# SCB_PLLs.net
KiCad netlist of a schematic drawn in Altium Designer
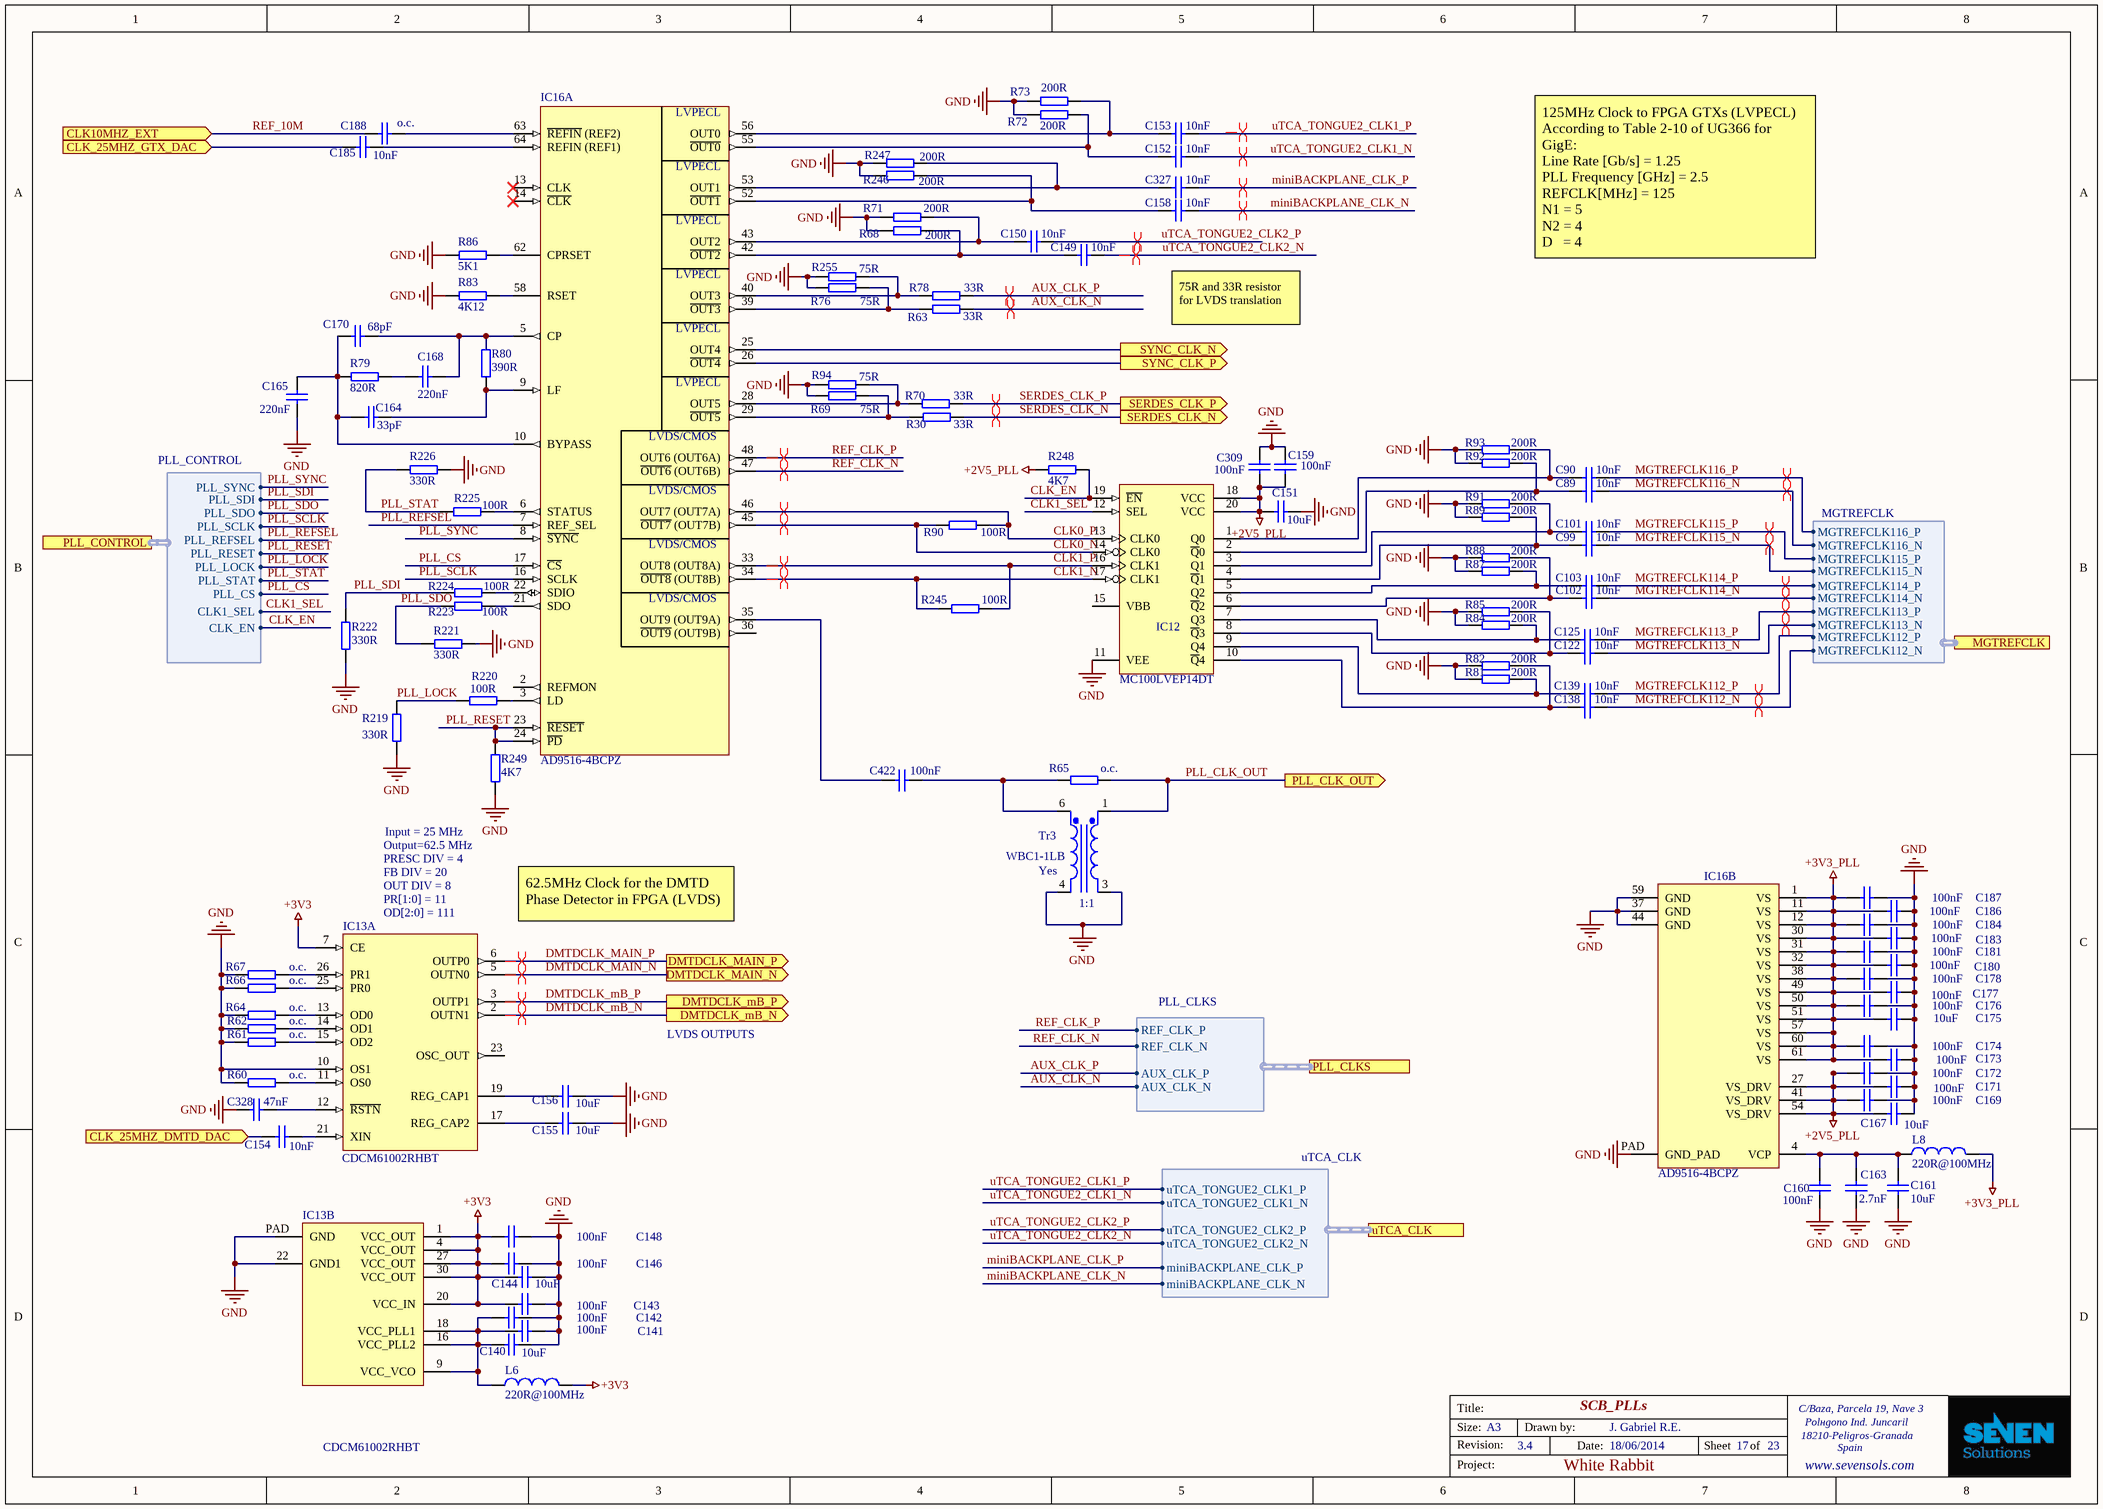
[diagram p0: SCB_PLLs.SchDoc]

(export (version "E")
  (design (tool "Eeschema 10.0.6"))
  (components
    (comp (ref "C89")
      (value "10nF")
      (footprint "CC1005-0402")
      (description "Capacitor")
      (fields (field (name "TOLERANCE") "±10%") (field (name "VOLTAGE") "25V"))
      (libsource (lib "wr_switch") (part "Cap"))
    )
    (comp (ref "C90")
      (value "10nF")
      (footprint "CC1005-0402")
      (description "Capacitor")
      (fields (field (name "TOLERANCE") "±10%") (field (name "VOLTAGE") "25V"))
      (libsource (lib "wr_switch") (part "Cap"))
    )
    (comp (ref "C99")
      (value "10nF")
      (footprint "CC1005-0402")
      (description "Capacitor")
      (fields (field (name "TOLERANCE") "±10%") (field (name "VOLTAGE") "25V"))
      (libsource (lib "wr_switch") (part "Cap"))
    )
    (comp (ref "C101")
      (value "10nF")
      (footprint "CC1005-0402")
      (description "Capacitor")
      (fields (field (name "TOLERANCE") "±10%") (field (name "VOLTAGE") "25V"))
      (libsource (lib "wr_switch") (part "Cap"))
    )
    (comp (ref "C102")
      (value "10nF")
      (footprint "CC1005-0402")
      (description "Capacitor")
      (fields (field (name "TOLERANCE") "±10%") (field (name "VOLTAGE") "25V"))
      (libsource (lib "wr_switch") (part "Cap"))
    )
    (comp (ref "C103")
      (value "10nF")
      (footprint "CC1005-0402")
      (description "Capacitor")
      (fields (field (name "TOLERANCE") "±10%") (field (name "VOLTAGE") "25V"))
      (libsource (lib "wr_switch") (part "Cap"))
    )
    (comp (ref "C122")
      (value "10nF")
      (footprint "CC1005-0402")
      (description "Capacitor")
      (fields (field (name "TOLERANCE") "±10%") (field (name "VOLTAGE") "25V"))
      (libsource (lib "wr_switch") (part "Cap"))
    )
    (comp (ref "C125")
      (value "10nF")
      (footprint "CC1005-0402")
      (description "Capacitor")
      (fields (field (name "TOLERANCE") "±10%") (field (name "VOLTAGE") "25V"))
      (libsource (lib "wr_switch") (part "Cap"))
    )
    (comp (ref "C138")
      (value "10nF")
      (footprint "CC1005-0402")
      (description "Capacitor")
      (fields (field (name "TOLERANCE") "±10%") (field (name "VOLTAGE") "25V"))
      (libsource (lib "wr_switch") (part "Cap"))
    )
    (comp (ref "C139")
      (value "10nF")
      (footprint "CC1005-0402")
      (description "Capacitor")
      (fields (field (name "TOLERANCE") "±10%") (field (name "VOLTAGE") "25V"))
      (libsource (lib "wr_switch") (part "Cap"))
    )
    (comp (ref "C140")
      (value "10uF")
      (footprint "CC1608-0603")
      (description "Capacitor")
      (fields (field (name "TOLERANCE") "±20%") (field (name "VOLTAGE") "6.3V"))
      (libsource (lib "wr_switch") (part "Cap"))
    )
    (comp (ref "C141")
      (value "100nF")
      (footprint "CC1005-0402")
      (description "Capacitor")
      (fields (field (name "TOLERANCE") "±10%") (field (name "VOLTAGE") "16V"))
      (libsource (lib "wr_switch") (part "Cap"))
    )
    (comp (ref "C142")
      (value "100nF")
      (footprint "CC1005-0402")
      (description "Capacitor")
      (fields (field (name "TOLERANCE") "±10%") (field (name "VOLTAGE") "16V"))
      (libsource (lib "wr_switch") (part "Cap"))
    )
    (comp (ref "C143")
      (value "100nF")
      (footprint "CC1005-0402")
      (description "Capacitor")
      (fields (field (name "TOLERANCE") "±10%") (field (name "VOLTAGE") "16V"))
      (libsource (lib "wr_switch") (part "Cap"))
    )
    (comp (ref "C144")
      (value "10uF")
      (footprint "CC1608-0603")
      (description "Capacitor")
      (fields (field (name "TOLERANCE") "±20%") (field (name "VOLTAGE") "6.3V"))
      (libsource (lib "wr_switch") (part "Cap"))
    )
    (comp (ref "C146")
      (value "100nF")
      (footprint "CC1005-0402")
      (description "Capacitor")
      (fields (field (name "TOLERANCE") "±10%") (field (name "VOLTAGE") "16V"))
      (libsource (lib "wr_switch") (part "Cap"))
    )
    (comp (ref "C148")
      (value "100nF")
      (footprint "CC1005-0402")
      (description "Capacitor")
      (fields (field (name "TOLERANCE") "±10%") (field (name "VOLTAGE") "16V"))
      (libsource (lib "wr_switch") (part "Cap"))
    )
    (comp (ref "C149")
      (value "10nF")
      (footprint "CC1005-0402")
      (description "Capacitor")
      (fields (field (name "TOLERANCE") "±10%") (field (name "VOLTAGE") "25V"))
      (libsource (lib "wr_switch") (part "Cap"))
    )
    (comp (ref "C150")
      (value "10nF")
      (footprint "CC1005-0402")
      (description "Capacitor")
      (fields (field (name "TOLERANCE") "±10%") (field (name "VOLTAGE") "25V"))
      (libsource (lib "wr_switch") (part "Cap"))
    )
    (comp (ref "C151")
      (value "10uF")
      (footprint "CC1608-0603")
      (description "Capacitor")
      (fields (field (name "TOLERANCE") "±20%") (field (name "VOLTAGE") "6.3V"))
      (libsource (lib "wr_switch") (part "Cap"))
    )
    (comp (ref "C152")
      (value "10nF")
      (footprint "CC1005-0402")
      (description "Capacitor")
      (fields (field (name "TOLERANCE") "±10%") (field (name "VOLTAGE") "25V"))
      (libsource (lib "wr_switch") (part "Cap"))
    )
    (comp (ref "C153")
      (value "10nF")
      (footprint "CC1005-0402")
      (description "Capacitor")
      (fields (field (name "TOLERANCE") "±10%") (field (name "VOLTAGE") "25V"))
      (libsource (lib "wr_switch") (part "Cap"))
    )
    (comp (ref "C154")
      (value "10nF")
      (footprint "CC1005-0402")
      (description "Capacitor")
      (fields (field (name "TOLERANCE") "±10%") (field (name "VOLTAGE") "25V"))
      (libsource (lib "wr_switch") (part "Cap"))
    )
    (comp (ref "C155")
      (value "10uF")
      (footprint "CC1608-0603")
      (description "Capacitor")
      (fields (field (name "TOLERANCE") "±20%") (field (name "VOLTAGE") "6.3V"))
      (libsource (lib "wr_switch") (part "Cap"))
    )
    (comp (ref "C156")
      (value "10uF")
      (footprint "CC1608-0603")
      (description "Capacitor")
      (fields (field (name "TOLERANCE") "±20%") (field (name "VOLTAGE") "6.3V"))
      (libsource (lib "wr_switch") (part "Cap"))
    )
    (comp (ref "C158")
      (value "10nF")
      (footprint "CC1005-0402")
      (description "Capacitor")
      (fields (field (name "TOLERANCE") "±10%") (field (name "VOLTAGE") "25V"))
      (libsource (lib "wr_switch") (part "Cap"))
    )
    (comp (ref "C159")
      (value "100nF")
      (footprint "CC1005-0402")
      (description "Capacitor")
      (fields (field (name "TOLERANCE") "±10%") (field (name "VOLTAGE") "16V"))
      (libsource (lib "wr_switch") (part "Cap"))
    )
    (comp (ref "C160")
      (value "100nF")
      (footprint "CC1005-0402")
      (description "Capacitor")
      (fields (field (name "TOLERANCE") "±10%") (field (name "VOLTAGE") "16V"))
      (libsource (lib "wr_switch") (part "Cap"))
    )
    (comp (ref "C161")
      (value "10uF")
      (footprint "CC1608-0603")
      (description "Capacitor")
      (fields (field (name "TOLERANCE") "±20%") (field (name "VOLTAGE") "6.3V"))
      (libsource (lib "wr_switch") (part "Cap"))
    )
    (comp (ref "C163")
      (value "2.7nF")
      (footprint "CC1005-0402")
      (description "Capacitor")
      (fields (field (name "TOLERANCE") "±10%") (field (name "VOLTAGE") "50V"))
      (libsource (lib "wr_switch") (part "Cap"))
    )
    (comp (ref "C164")
      (value "33pF")
      (footprint "CC1608-0603")
      (description "Capacitor")
      (fields (field (name "TOLERANCE") "±5%") (field (name "VOLTAGE") "50V"))
      (libsource (lib "wr_switch") (part "Cap"))
    )
    (comp (ref "C165")
      (value "220nF")
      (footprint "CC1608-0603")
      (description "Capacitor")
      (fields (field (name "TOLERANCE") "±10%") (field (name "VOLTAGE") "10V"))
      (libsource (lib "wr_switch") (part "Cap"))
    )
    (comp (ref "C167")
      (value "10uF")
      (footprint "CC1608-0603")
      (description "Capacitor")
      (fields (field (name "TOLERANCE") "±20%") (field (name "VOLTAGE") "6.3V"))
      (libsource (lib "wr_switch") (part "Cap"))
    )
    (comp (ref "C168")
      (value "220nF")
      (footprint "CC1608-0603")
      (description "Capacitor")
      (fields (field (name "TOLERANCE") "±10%") (field (name "VOLTAGE") "10V"))
      (libsource (lib "wr_switch") (part "Cap"))
    )
    (comp (ref "C169")
      (value "100nF")
      (footprint "CC1005-0402")
      (description "Capacitor")
      (fields (field (name "TOLERANCE") "±10%") (field (name "VOLTAGE") "16V"))
      (libsource (lib "wr_switch") (part "Cap"))
    )
    (comp (ref "C170")
      (value "68pF")
      (footprint "CC1608-0603")
      (description "Capacitor")
      (fields (field (name "TOLERANCE") "±5%") (field (name "VOLTAGE") "50V"))
      (libsource (lib "wr_switch") (part "Cap"))
    )
    (comp (ref "C171")
      (value "100nF")
      (footprint "CC1005-0402")
      (description "Capacitor")
      (fields (field (name "TOLERANCE") "±10%") (field (name "VOLTAGE") "16V"))
      (libsource (lib "wr_switch") (part "Cap"))
    )
    (comp (ref "C172")
      (value "100nF")
      (footprint "CC1005-0402")
      (description "Capacitor")
      (fields (field (name "TOLERANCE") "±10%") (field (name "VOLTAGE") "16V"))
      (libsource (lib "wr_switch") (part "Cap"))
    )
    (comp (ref "C173")
      (value "100nF")
      (footprint "CC1005-0402")
      (description "Capacitor")
      (fields (field (name "TOLERANCE") "±10%") (field (name "VOLTAGE") "16V"))
      (libsource (lib "wr_switch") (part "Cap"))
    )
    (comp (ref "C174")
      (value "100nF")
      (footprint "CC1005-0402")
      (description "Capacitor")
      (fields (field (name "TOLERANCE") "±10%") (field (name "VOLTAGE") "16V"))
      (libsource (lib "wr_switch") (part "Cap"))
    )
    (comp (ref "C175")
      (value "10uF")
      (footprint "CC1608-0603")
      (description "Capacitor")
      (fields (field (name "TOLERANCE") "±20%") (field (name "VOLTAGE") "6.3V"))
      (libsource (lib "wr_switch") (part "Cap"))
    )
    (comp (ref "C176")
      (value "100nF")
      (footprint "CC1005-0402")
      (description "Capacitor")
      (fields (field (name "TOLERANCE") "±10%") (field (name "VOLTAGE") "16V"))
      (libsource (lib "wr_switch") (part "Cap"))
    )
    (comp (ref "C177")
      (value "100nF")
      (footprint "CC1005-0402")
      (description "Capacitor")
      (fields (field (name "TOLERANCE") "±10%") (field (name "VOLTAGE") "16V"))
      (libsource (lib "wr_switch") (part "Cap"))
    )
    (comp (ref "C178")
      (value "100nF")
      (footprint "CC1005-0402")
      (description "Capacitor")
      (fields (field (name "TOLERANCE") "±10%") (field (name "VOLTAGE") "16V"))
      (libsource (lib "wr_switch") (part "Cap"))
    )
    (comp (ref "C180")
      (value "100nF")
      (footprint "CC1005-0402")
      (description "Capacitor")
      (fields (field (name "TOLERANCE") "±10%") (field (name "VOLTAGE") "16V"))
      (libsource (lib "wr_switch") (part "Cap"))
    )
    (comp (ref "C181")
      (value "100nF")
      (footprint "CC1005-0402")
      (description "Capacitor")
      (fields (field (name "TOLERANCE") "±10%") (field (name "VOLTAGE") "16V"))
      (libsource (lib "wr_switch") (part "Cap"))
    )
    (comp (ref "C183")
      (value "100nF")
      (footprint "CC1005-0402")
      (description "Capacitor")
      (fields (field (name "TOLERANCE") "±10%") (field (name "VOLTAGE") "16V"))
      (libsource (lib "wr_switch") (part "Cap"))
    )
    (comp (ref "C184")
      (value "100nF")
      (footprint "CC1005-0402")
      (description "Capacitor")
      (fields (field (name "TOLERANCE") "±10%") (field (name "VOLTAGE") "16V"))
      (libsource (lib "wr_switch") (part "Cap"))
    )
    (comp (ref "C185")
      (value "10nF")
      (footprint "CC1005-0402")
      (description "Capacitor")
      (fields (field (name "TOLERANCE") "±10%") (field (name "VOLTAGE") "25V"))
      (libsource (lib "wr_switch") (part "Cap"))
    )
    (comp (ref "C186")
      (value "100nF")
      (footprint "CC1005-0402")
      (description "Capacitor")
      (fields (field (name "TOLERANCE") "±10%") (field (name "VOLTAGE") "16V"))
      (libsource (lib "wr_switch") (part "Cap"))
    )
    (comp (ref "C187")
      (value "100nF")
      (footprint "CC1005-0402")
      (description "Capacitor")
      (fields (field (name "TOLERANCE") "±10%") (field (name "VOLTAGE") "16V"))
      (libsource (lib "wr_switch") (part "Cap"))
    )
    (comp (ref "C188")
      (value "o.c.")
      (footprint "CC1005-0402")
      (description "Capacitor")
      (fields (field (name "TOLERANCE") "±10%") (field (name "VOLTAGE") "25V"))
      (libsource (lib "wr_switch") (part "Cap"))
    )
    (comp (ref "C309")
      (value "100nF")
      (footprint "CC1005-0402")
      (description "Capacitor")
      (fields (field (name "TOLERANCE") "±10%") (field (name "VOLTAGE") "16V"))
      (libsource (lib "wr_switch") (part "Cap"))
    )
    (comp (ref "C327")
      (value "10nF")
      (footprint "CC1005-0402")
      (description "Capacitor")
      (fields (field (name "TOLERANCE") "±10%") (field (name "VOLTAGE") "25V"))
      (libsource (lib "wr_switch") (part "Cap"))
    )
    (comp (ref "C328")
      (value "47nF")
      (footprint "CC1005-0402")
      (description "Capacitor")
      (fields (field (name "TOLERANCE") "±10%") (field (name "VOLTAGE") "25V"))
      (libsource (lib "wr_switch") (part "Cap"))
    )
    (comp (ref "C422")
      (value "100nF")
      (footprint "CC1005-0402")
      (description "Capacitor")
      (fields (field (name "TOLERANCE") "±10%") (field (name "VOLTAGE") "16V"))
      (libsource (lib "wr_switch") (part "Cap"))
    )
    (comp (ref "IC12")
      (value "MC100LVEP14DT")
      (footprint "948E-02_N")
      (description "Low-Voltage 1:5 Differential LVECL/LVPECL/LVEPECL/HSTL Clock Driver")
      (libsource (lib "ON Semi Peripheral Clock Generator") (part "MC100LVEP14DT"))
    )
    (comp (ref "IC13")
      (value "CDCM61002RHBT")
      (footprint "QFN32_POWERPAD")
      (description "Low Jitter Clock Generator, Two Outpust, Integrated VCO")
      (fields (field (name "MANUFACTURER") "Texas Instruments"))
      (libsource (lib "wr_switch") (part "CDCM61002"))
    )
    (comp (ref "IC16")
      (value "AD9516-4BCPZ")
      (footprint "QFN50P900X900X100-64M")
      (description "PLL with clock fanout")
      (libsource (lib "wr_switch") (part "AD9516"))
    )
    (comp (ref "L6")
      (value "220R@100MHz Ferrite Bead")
      (footprint "0603")
      (description "ferrite bead")
      (fields (field (name "IMPEDANCE") "220R@100MHz"))
      (libsource (lib "wr_switch") (part "L_FERRITE_BEAD"))
    )
    (comp (ref "L8")
      (value "220R@100MHz Ferrite Bead")
      (footprint "0603")
      (description "ferrite bead")
      (fields (field (name "IMPEDANCE") "220R@100MHz"))
      (libsource (lib "wr_switch") (part "L_FERRITE_BEAD"))
    )
    (comp (ref "R30")
      (value "33R")
      (footprint "0402")
      (description "SMD Resistor")
      (fields (field (name "TOLERANCE") "±1%"))
      (libsource (lib "wr_switch") (part "RES_SMD"))
    )
    (comp (ref "R60")
      (value "o.c.")
      (footprint "0402")
      (description "SMD Resistor")
      (libsource (lib "wr_switch") (part "RES_SMD"))
    )
    (comp (ref "R61")
      (value "o.c.")
      (footprint "0402")
      (description "SMD Resistor")
      (libsource (lib "wr_switch") (part "RES_SMD"))
    )
    (comp (ref "R62")
      (value "o.c.")
      (footprint "0402")
      (description "SMD Resistor")
      (libsource (lib "wr_switch") (part "RES_SMD"))
    )
    (comp (ref "R63")
      (value "33R")
      (footprint "0402")
      (description "SMD Resistor")
      (fields (field (name "TOLERANCE") "±1%"))
      (libsource (lib "wr_switch") (part "RES_SMD"))
    )
    (comp (ref "R64")
      (value "o.c.")
      (footprint "0402")
      (description "SMD Resistor")
      (libsource (lib "wr_switch") (part "RES_SMD"))
    )
    (comp (ref "R65")
      (value "o.c.")
      (footprint "0402")
      (description "SMD Resistor")
      (libsource (lib "wr_switch") (part "RES_SMD"))
    )
    (comp (ref "R66")
      (value "o.c.")
      (footprint "0402")
      (description "SMD Resistor")
      (libsource (lib "wr_switch") (part "RES_SMD"))
    )
    (comp (ref "R67")
      (value "o.c.")
      (footprint "0402")
      (description "SMD Resistor")
      (libsource (lib "wr_switch") (part "RES_SMD"))
    )
    (comp (ref "R68")
      (value "200R")
      (footprint "0402")
      (description "SMD Resistor")
      (fields (field (name "TOLERANCE") "±1%"))
      (libsource (lib "wr_switch") (part "RES_SMD"))
    )
    (comp (ref "R69")
      (value "75R")
      (footprint "0402")
      (description "SMD Resistor")
      (fields (field (name "TOLERANCE") "±1%"))
      (libsource (lib "wr_switch") (part "RES_SMD"))
    )
    (comp (ref "R70")
      (value "33R")
      (footprint "0402")
      (description "SMD Resistor")
      (fields (field (name "TOLERANCE") "±1%"))
      (libsource (lib "wr_switch") (part "RES_SMD"))
    )
    (comp (ref "R71")
      (value "200R")
      (footprint "0402")
      (description "SMD Resistor")
      (fields (field (name "TOLERANCE") "±1%"))
      (libsource (lib "wr_switch") (part "RES_SMD"))
    )
    (comp (ref "R72")
      (value "200R")
      (footprint "0402")
      (description "SMD Resistor")
      (fields (field (name "TOLERANCE") "±1%"))
      (libsource (lib "wr_switch") (part "RES_SMD"))
    )
    (comp (ref "R73")
      (value "200R")
      (footprint "0402")
      (description "SMD Resistor")
      (fields (field (name "TOLERANCE") "±1%"))
      (libsource (lib "wr_switch") (part "RES_SMD"))
    )
    (comp (ref "R76")
      (value "75R")
      (footprint "0402")
      (description "SMD Resistor")
      (fields (field (name "TOLERANCE") "±1%"))
      (libsource (lib "wr_switch") (part "RES_SMD"))
    )
    (comp (ref "R78")
      (value "33R")
      (footprint "0402")
      (description "SMD Resistor")
      (fields (field (name "TOLERANCE") "±1%"))
      (libsource (lib "wr_switch") (part "RES_SMD"))
    )
    (comp (ref "R79")
      (value "820R")
      (footprint "0603")
      (description "SMD Resistor")
      (fields (field (name "TOLERANCE") "±1%"))
      (libsource (lib "wr_switch") (part "RES_SMD"))
    )
    (comp (ref "R80")
      (value "390R")
      (footprint "0603")
      (description "SMD Resistor")
      (fields (field (name "TOLERANCE") "±1%"))
      (libsource (lib "wr_switch") (part "RES_SMD"))
    )
    (comp (ref "R81")
      (value "200R")
      (footprint "0402")
      (description "SMD Resistor")
      (fields (field (name "TOLERANCE") "±1%"))
      (libsource (lib "wr_switch") (part "RES_SMD"))
    )
    (comp (ref "R82")
      (value "200R")
      (footprint "0402")
      (description "SMD Resistor")
      (fields (field (name "TOLERANCE") "±1%"))
      (libsource (lib "wr_switch") (part "RES_SMD"))
    )
    (comp (ref "R83")
      (value "4K12")
      (footprint "0402")
      (description "SMD Resistor")
      (fields (field (name "TOLERANCE") "±1%"))
      (libsource (lib "wr_switch") (part "RES_SMD"))
    )
    (comp (ref "R84")
      (value "200R")
      (footprint "0402")
      (description "SMD Resistor")
      (fields (field (name "TOLERANCE") "±1%"))
      (libsource (lib "wr_switch") (part "RES_SMD"))
    )
    (comp (ref "R85")
      (value "200R")
      (footprint "0402")
      (description "SMD Resistor")
      (fields (field (name "TOLERANCE") "±1%"))
      (libsource (lib "wr_switch") (part "RES_SMD"))
    )
    (comp (ref "R86")
      (value "5K1")
      (footprint "0402")
      (description "SMD Resistor")
      (fields (field (name "TOLERANCE") "±1%"))
      (libsource (lib "wr_switch") (part "RES_SMD"))
    )
    (comp (ref "R87")
      (value "200R")
      (footprint "0402")
      (description "SMD Resistor")
      (fields (field (name "TOLERANCE") "±1%"))
      (libsource (lib "wr_switch") (part "RES_SMD"))
    )
    (comp (ref "R88")
      (value "200R")
      (footprint "0402")
      (description "SMD Resistor")
      (fields (field (name "TOLERANCE") "±1%"))
      (libsource (lib "wr_switch") (part "RES_SMD"))
    )
    (comp (ref "R89")
      (value "200R")
      (footprint "0402")
      (description "SMD Resistor")
      (fields (field (name "TOLERANCE") "±1%"))
      (libsource (lib "wr_switch") (part "RES_SMD"))
    )
    (comp (ref "R90")
      (value "100R")
      (footprint "0402")
      (description "SMD Resistor")
      (fields (field (name "TOLERANCE") "±1%"))
      (libsource (lib "wr_switch") (part "RES_SMD"))
    )
    (comp (ref "R91")
      (value "200R")
      (footprint "0402")
      (description "SMD Resistor")
      (fields (field (name "TOLERANCE") "±1%"))
      (libsource (lib "wr_switch") (part "RES_SMD"))
    )
    (comp (ref "R92")
      (value "200R")
      (footprint "0402")
      (description "SMD Resistor")
      (fields (field (name "TOLERANCE") "±1%"))
      (libsource (lib "wr_switch") (part "RES_SMD"))
    )
    (comp (ref "R93")
      (value "200R")
      (footprint "0402")
      (description "SMD Resistor")
      (fields (field (name "TOLERANCE") "±1%"))
      (libsource (lib "wr_switch") (part "RES_SMD"))
    )
    (comp (ref "R94")
      (value "75R")
      (footprint "0402")
      (description "SMD Resistor")
      (fields (field (name "TOLERANCE") "±1%"))
      (libsource (lib "wr_switch") (part "RES_SMD"))
    )
    (comp (ref "R219")
      (value "330R")
      (footprint "0402")
      (description "SMD Resistor")
      (fields (field (name "TOLERANCE") "±1%"))
      (libsource (lib "wr_switch") (part "RES_SMD"))
    )
    (comp (ref "R220")
      (value "100R")
      (footprint "0402")
      (description "SMD Resistor")
      (fields (field (name "TOLERANCE") "±1%"))
      (libsource (lib "wr_switch") (part "RES_SMD"))
    )
    (comp (ref "R221")
      (value "330R")
      (footprint "0402")
      (description "SMD Resistor")
      (fields (field (name "TOLERANCE") "±1%"))
      (libsource (lib "wr_switch") (part "RES_SMD"))
    )
    (comp (ref "R222")
      (value "330R")
      (footprint "0402")
      (description "SMD Resistor")
      (fields (field (name "TOLERANCE") "±1%"))
      (libsource (lib "wr_switch") (part "RES_SMD"))
    )
    (comp (ref "R223")
      (value "100R")
      (footprint "0402")
      (description "SMD Resistor")
      (fields (field (name "TOLERANCE") "±1%"))
      (libsource (lib "wr_switch") (part "RES_SMD"))
    )
    (comp (ref "R224")
      (value "100R")
      (footprint "0402")
      (description "SMD Resistor")
      (fields (field (name "TOLERANCE") "±1%"))
      (libsource (lib "wr_switch") (part "RES_SMD"))
    )
    (comp (ref "R225")
      (value "100R")
      (footprint "0402")
      (description "SMD Resistor")
      (fields (field (name "TOLERANCE") "±1%"))
      (libsource (lib "wr_switch") (part "RES_SMD"))
    )
    (comp (ref "R226")
      (value "330R")
      (footprint "0402")
      (description "SMD Resistor")
      (fields (field (name "TOLERANCE") "±1%"))
      (libsource (lib "wr_switch") (part "RES_SMD"))
    )
    (comp (ref "R245")
      (value "100R")
      (footprint "0402")
      (description "SMD Resistor")
      (fields (field (name "TOLERANCE") "±1%"))
      (libsource (lib "wr_switch") (part "RES_SMD"))
    )
    (comp (ref "R246")
      (value "200R")
      (footprint "0402")
      (description "SMD Resistor")
      (fields (field (name "TOLERANCE") "±1%"))
      (libsource (lib "wr_switch") (part "RES_SMD"))
    )
    (comp (ref "R247")
      (value "200R")
      (footprint "0402")
      (description "SMD Resistor")
      (fields (field (name "TOLERANCE") "±1%"))
      (libsource (lib "wr_switch") (part "RES_SMD"))
    )
    (comp (ref "R248")
      (value "4K7")
      (footprint "0402")
      (description "SMD Resistor")
      (fields (field (name "TOLERANCE") "±1%"))
      (libsource (lib "wr_switch") (part "RES_SMD"))
    )
    (comp (ref "R249")
      (value "4K7")
      (footprint "0402")
      (description "SMD Resistor")
      (fields (field (name "TOLERANCE") "±1%"))
      (libsource (lib "wr_switch") (part "RES_SMD"))
    )
    (comp (ref "R255")
      (value "75R")
      (footprint "0402")
      (description "SMD Resistor")
      (fields (field (name "TOLERANCE") "±1%"))
      (libsource (lib "wr_switch") (part "RES_SMD"))
    )
    (comp (ref "Tr3")
      (value "WBC1-1LB")
      (footprint "SMT6P150P")
      (description "SMT Mini WideBand Transformer 1:1, 10uH,")
      (fields
        (field (name "MANUFACTURER") "Coilcraft")
        (field (name "ALTIUM_VALUE") "1:1")
        (field (name "MOUNTED") "Yes")
      )
      (libsource (lib "wr_switch") (part "WBC1-1LB"))
    )
  )
  (nets
    (net (code "5") (name "+2V5_PLL") (class "Default")
      (node (ref "C151") (pin "2") (pinfunction "2_2") (pintype "passive"))
      (node (ref "C159") (pin "2") (pinfunction "2_2") (pintype "passive"))
      (node (ref "C167") (pin "1") (pinfunction "1_1") (pintype "passive"))
      (node (ref "C169") (pin "2") (pinfunction "2_2") (pintype "passive"))
      (node (ref "C171") (pin "2") (pinfunction "2_2") (pintype "passive"))
      (node (ref "C172") (pin "2") (pinfunction "2_2") (pintype "passive"))
      (node (ref "C309") (pin "2") (pinfunction "2_2") (pintype "passive"))
      (node (ref "IC12") (pin "18") (pinfunction "VCC_18") (pintype "power_in"))
      (node (ref "IC12") (pin "20") (pinfunction "VCC_20") (pintype "power_in"))
      (node (ref "IC16") (pin "27") (pinfunction "VS_DRV_27") (pintype "power_in"))
      (node (ref "IC16") (pin "41") (pinfunction "VS_DRV_41") (pintype "power_in"))
      (node (ref "IC16") (pin "54") (pinfunction "VS_DRV_54") (pintype "power_in"))
      (node (ref "R248") (pin "2") (pinfunction "2_2") (pintype "passive"))
    )
    (net (code "6") (name "+3V3") (class "Default")
      (node (ref "C143") (pin "2") (pinfunction "2_2") (pintype "passive"))
      (node (ref "C144") (pin "1") (pinfunction "1_1") (pintype "passive"))
      (node (ref "C146") (pin "2") (pinfunction "2_2") (pintype "passive"))
      (node (ref "C148") (pin "2") (pinfunction "2_2") (pintype "passive"))
      (node (ref "IC13") (pin "1") (pinfunction "VCC_OUT_1") (pintype "power_in"))
      (node (ref "IC13") (pin "20") (pinfunction "VCC_IN_20") (pintype "power_in"))
      (node (ref "IC13") (pin "27") (pinfunction "VCC_OUT_27") (pintype "power_in"))
      (node (ref "IC13") (pin "30") (pinfunction "VCC_OUT_30") (pintype "power_in"))
      (node (ref "IC13") (pin "4") (pinfunction "VCC_OUT_4") (pintype "power_in"))
      (node (ref "IC13") (pin "7") (pinfunction "CE_7") (pintype "input"))
      (node (ref "L6") (pin "2") (pinfunction "2_2") (pintype "passive"))
    )
    (net (code "7") (name "+3V3_PLL") (class "Default")
      (node (ref "C173") (pin "2") (pinfunction "2_2") (pintype "passive"))
      (node (ref "C174") (pin "2") (pinfunction "2_2") (pintype "passive"))
      (node (ref "C175") (pin "1") (pinfunction "1_1") (pintype "passive"))
      (node (ref "C176") (pin "2") (pinfunction "2_2") (pintype "passive"))
      (node (ref "C177") (pin "2") (pinfunction "2_2") (pintype "passive"))
      (node (ref "C178") (pin "2") (pinfunction "2_2") (pintype "passive"))
      (node (ref "C180") (pin "2") (pinfunction "2_2") (pintype "passive"))
      (node (ref "C181") (pin "2") (pinfunction "2_2") (pintype "passive"))
      (node (ref "C183") (pin "2") (pinfunction "2_2") (pintype "passive"))
      (node (ref "C184") (pin "2") (pinfunction "2_2") (pintype "passive"))
      (node (ref "C186") (pin "2") (pinfunction "2_2") (pintype "passive"))
      (node (ref "C187") (pin "2") (pinfunction "2_2") (pintype "passive"))
      (node (ref "IC16") (pin "1") (pinfunction "VS_1") (pintype "power_in"))
      (node (ref "IC16") (pin "11") (pinfunction "VS_11") (pintype "power_in"))
      (node (ref "IC16") (pin "12") (pinfunction "VS_12") (pintype "power_in"))
      (node (ref "IC16") (pin "30") (pinfunction "VS_30") (pintype "power_in"))
      (node (ref "IC16") (pin "31") (pinfunction "VS_31") (pintype "power_in"))
      (node (ref "IC16") (pin "32") (pinfunction "VS_32") (pintype "power_in"))
      (node (ref "IC16") (pin "38") (pinfunction "VS_38") (pintype "power_in"))
      (node (ref "IC16") (pin "49") (pinfunction "VS_49") (pintype "power_in"))
      (node (ref "IC16") (pin "50") (pinfunction "VS_50") (pintype "power_in"))
      (node (ref "IC16") (pin "51") (pinfunction "VS_51") (pintype "power_in"))
      (node (ref "IC16") (pin "57") (pinfunction "VS_57") (pintype "power_in"))
      (node (ref "IC16") (pin "60") (pinfunction "VS_60") (pintype "power_in"))
      (node (ref "IC16") (pin "61") (pinfunction "VS_61") (pintype "power_in"))
      (node (ref "L8") (pin "2") (pinfunction "2_2") (pintype "passive"))
    )
    (net (code "8") (name "/AUX_CLK_N") (class "Default")
      (node (ref "R63") (pin "2") (pinfunction "2_2") (pintype "passive"))
    )
    (net (code "9") (name "/AUX_CLK_P") (class "Default")
      (node (ref "R78") (pin "2") (pinfunction "2_2") (pintype "passive"))
    )
    (net (code "10") (name "/CLK0_N") (class "Default")
      (node (ref "IC12") (pin "14") (pinfunction "CLK0_14") (pintype "input"))
      (node (ref "IC16") (pin "45") (pinfunction "~{OUT7}_(OUT7B)_45") (pintype "output"))
      (node (ref "R90") (pin "1") (pinfunction "1_1") (pintype "passive"))
    )
    (net (code "11") (name "/CLK0_P") (class "Default")
      (node (ref "IC12") (pin "13") (pinfunction "CLK0_13") (pintype "input"))
      (node (ref "IC16") (pin "46") (pinfunction "OUT7_(OUT7A)_46") (pintype "output"))
      (node (ref "R90") (pin "2") (pinfunction "2_2") (pintype "passive"))
    )
    (net (code "12") (name "/CLK1_N") (class "Default")
      (node (ref "IC12") (pin "17") (pinfunction "CLK1_17") (pintype "input"))
      (node (ref "IC16") (pin "34") (pinfunction "~{OUT8}_(OUT8B)_34") (pintype "output"))
      (node (ref "R245") (pin "1") (pinfunction "1_1") (pintype "passive"))
    )
    (net (code "13") (name "/CLK1_P") (class "Default")
      (node (ref "IC12") (pin "16") (pinfunction "CLK1_16") (pintype "input"))
      (node (ref "IC16") (pin "33") (pinfunction "OUT8_(OUT8A)_33") (pintype "output"))
      (node (ref "R245") (pin "2") (pinfunction "2_2") (pintype "passive"))
    )
    (net (code "14") (name "/CLK1_SEL") (class "Default")
      (node (ref "IC12") (pin "12") (pinfunction "SEL_12") (pintype "input"))
    )
    (net (code "15") (name "/CLK_25MHZ_DMTD_DAC") (class "Default")
      (node (ref "C154") (pin "2") (pinfunction "2_2") (pintype "passive"))
    )
    (net (code "16") (name "/CLK_25MHZ_GTX_DAC") (class "Default")
      (node (ref "C185") (pin "1") (pinfunction "1_1") (pintype "passive"))
    )
    (net (code "17") (name "/CLK_EN") (class "Default")
      (node (ref "IC12") (pin "19") (pinfunction "~{EN}_19") (pintype "input"))
      (node (ref "R248") (pin "1") (pinfunction "1_1") (pintype "passive"))
    )
    (net (code "18") (name "/DMTDCLK_MAIN_N") (class "Default")
      (node (ref "IC13") (pin "5") (pinfunction "OUTN0_5") (pintype "output"))
    )
    (net (code "19") (name "/DMTDCLK_MAIN_P") (class "Default")
      (node (ref "IC13") (pin "6") (pinfunction "OUTP0_6") (pintype "output"))
    )
    (net (code "20") (name "/DMTDCLK_mB_N") (class "Default")
      (node (ref "IC13") (pin "2") (pinfunction "OUTN1_2") (pintype "output"))
    )
    (net (code "21") (name "/DMTDCLK_mB_P") (class "Default")
      (node (ref "IC13") (pin "3") (pinfunction "OUTP1_3") (pintype "output"))
    )
    (net (code "22") (name "/MGTREFCLK112_N") (class "Default")
      (node (ref "C138") (pin "1") (pinfunction "1_1") (pintype "passive"))
    )
    (net (code "23") (name "/MGTREFCLK112_P") (class "Default")
      (node (ref "C139") (pin "1") (pinfunction "1_1") (pintype "passive"))
    )
    (net (code "24") (name "/MGTREFCLK113_N") (class "Default")
      (node (ref "C122") (pin "1") (pinfunction "1_1") (pintype "passive"))
    )
    (net (code "25") (name "/MGTREFCLK113_P") (class "Default")
      (node (ref "C125") (pin "1") (pinfunction "1_1") (pintype "passive"))
    )
    (net (code "26") (name "/MGTREFCLK114_N") (class "Default")
      (node (ref "C102") (pin "1") (pinfunction "1_1") (pintype "passive"))
    )
    (net (code "27") (name "/MGTREFCLK114_P") (class "Default")
      (node (ref "C103") (pin "1") (pinfunction "1_1") (pintype "passive"))
    )
    (net (code "28") (name "/MGTREFCLK115_N") (class "Default")
      (node (ref "C99") (pin "1") (pinfunction "1_1") (pintype "passive"))
    )
    (net (code "29") (name "/MGTREFCLK115_P") (class "Default")
      (node (ref "C101") (pin "1") (pinfunction "1_1") (pintype "passive"))
    )
    (net (code "30") (name "/MGTREFCLK116_N") (class "Default")
      (node (ref "C89") (pin "1") (pinfunction "1_1") (pintype "passive"))
    )
    (net (code "31") (name "/MGTREFCLK116_P") (class "Default")
      (node (ref "C90") (pin "1") (pinfunction "1_1") (pintype "passive"))
    )
    (net (code "32") (name "/PLL_CLK_OUT") (class "Default")
      (node (ref "R65") (pin "1") (pinfunction "1_1") (pintype "passive"))
      (node (ref "Tr3") (pin "1") (pinfunction "Sec+_1") (pintype "passive"))
    )
    (net (code "33") (name "/PLL_CS") (class "Default")
      (node (ref "IC16") (pin "17") (pinfunction "~{CS}_17") (pintype "input"))
    )
    (net (code "34") (name "/PLL_LOCK") (class "Default")
      (node (ref "R219") (pin "2") (pinfunction "2_2") (pintype "passive"))
      (node (ref "R220") (pin "2") (pinfunction "2_2") (pintype "passive"))
    )
    (net (code "35") (name "/PLL_REFSEL") (class "Default")
      (node (ref "IC16") (pin "7") (pinfunction "REF_SEL_7") (pintype "input"))
    )
    (net (code "36") (name "/PLL_RESET") (class "Default")
      (node (ref "IC16") (pin "23") (pinfunction "~{RESET}_23") (pintype "input"))
      (node (ref "IC16") (pin "24") (pinfunction "~{PD}_24") (pintype "input"))
      (node (ref "R249") (pin "2") (pinfunction "2_2") (pintype "passive"))
    )
    (net (code "37") (name "/PLL_SCLK") (class "Default")
      (node (ref "IC16") (pin "16") (pinfunction "SCLK_16") (pintype "input"))
    )
    (net (code "38") (name "/PLL_SDI") (class "Default")
      (node (ref "R222") (pin "2") (pinfunction "2_2") (pintype "passive"))
      (node (ref "R224") (pin "2") (pinfunction "2_2") (pintype "passive"))
    )
    (net (code "39") (name "/PLL_SDO") (class "Default")
      (node (ref "R221") (pin "2") (pinfunction "2_2") (pintype "passive"))
      (node (ref "R223") (pin "2") (pinfunction "2_2") (pintype "passive"))
    )
    (net (code "40") (name "/PLL_STAT") (class "Default")
      (node (ref "R225") (pin "2") (pinfunction "2_2") (pintype "passive"))
      (node (ref "R226") (pin "2") (pinfunction "2_2") (pintype "passive"))
    )
    (net (code "41") (name "/PLL_SYNC") (class "Default")
      (node (ref "IC16") (pin "8") (pinfunction "~{SYNC}_8") (pintype "input"))
    )
    (net (code "42") (name "/REF_10M") (class "Default")
      (node (ref "C188") (pin "1") (pinfunction "1_1") (pintype "passive"))
    )
    (net (code "43") (name "/REF_CLK_N") (class "Default")
      (node (ref "IC16") (pin "47") (pinfunction "~{OUT6}_(OUT6B)_47") (pintype "output"))
    )
    (net (code "44") (name "/REF_CLK_P") (class "Default")
      (node (ref "IC16") (pin "48") (pinfunction "OUT6_(OUT6A)_48") (pintype "output"))
    )
    (net (code "45") (name "/SERDES_CLK_N") (class "Default")
      (node (ref "R30") (pin "2") (pinfunction "2_2") (pintype "passive"))
    )
    (net (code "46") (name "/SERDES_CLK_P") (class "Default")
      (node (ref "R70") (pin "2") (pinfunction "2_2") (pintype "passive"))
    )
    (net (code "47") (name "/SYNC_CLK_N") (class "Default")
      (node (ref "IC16") (pin "25") (pinfunction "OUT4_25") (pintype "output"))
    )
    (net (code "48") (name "/SYNC_CLK_P") (class "Default")
      (node (ref "IC16") (pin "26") (pinfunction "~{OUT4}_26") (pintype "output"))
    )
    (net (code "49") (name "/miniBACKPLANE_CLK_N") (class "Default")
      (node (ref "C158") (pin "1") (pinfunction "1_1") (pintype "passive"))
    )
    (net (code "50") (name "/miniBACKPLANE_CLK_P") (class "Default")
      (node (ref "C327") (pin "1") (pinfunction "1_1") (pintype "passive"))
    )
    (net (code "51") (name "/uTCA_TONGUE2_CLK1_N") (class "Default")
      (node (ref "C152") (pin "1") (pinfunction "1_1") (pintype "passive"))
    )
    (net (code "52") (name "/uTCA_TONGUE2_CLK1_P") (class "Default")
      (node (ref "C153") (pin "1") (pinfunction "1_1") (pintype "passive"))
    )
    (net (code "53") (name "/uTCA_TONGUE2_CLK2_N") (class "Default")
      (node (ref "C149") (pin "1") (pinfunction "1_1") (pintype "passive"))
    )
    (net (code "54") (name "/uTCA_TONGUE2_CLK2_P") (class "Default")
      (node (ref "C150") (pin "1") (pinfunction "1_1") (pintype "passive"))
    )
    (net (code "59") (name "GND") (class "Default")
      (node (ref "C140") (pin "2") (pinfunction "2_2") (pintype "passive"))
      (node (ref "C141") (pin "1") (pinfunction "1_1") (pintype "passive"))
      (node (ref "C142") (pin "1") (pinfunction "1_1") (pintype "passive"))
      (node (ref "C143") (pin "1") (pinfunction "1_1") (pintype "passive"))
      (node (ref "C144") (pin "2") (pinfunction "2_2") (pintype "passive"))
      (node (ref "C146") (pin "1") (pinfunction "1_1") (pintype "passive"))
      (node (ref "C148") (pin "1") (pinfunction "1_1") (pintype "passive"))
      (node (ref "C151") (pin "1") (pinfunction "1_1") (pintype "passive"))
      (node (ref "C155") (pin "2") (pinfunction "2_2") (pintype "passive"))
      (node (ref "C156") (pin "2") (pinfunction "2_2") (pintype "passive"))
      (node (ref "C159") (pin "1") (pinfunction "1_1") (pintype "passive"))
      (node (ref "C160") (pin "2") (pinfunction "2_2") (pintype "passive"))
      (node (ref "C161") (pin "1") (pinfunction "1_1") (pintype "passive"))
      (node (ref "C163") (pin "1") (pinfunction "1_1") (pintype "passive"))
      (node (ref "C165") (pin "1") (pinfunction "1_1") (pintype "passive"))
      (node (ref "C167") (pin "2") (pinfunction "2_2") (pintype "passive"))
      (node (ref "C169") (pin "1") (pinfunction "1_1") (pintype "passive"))
      (node (ref "C171") (pin "1") (pinfunction "1_1") (pintype "passive"))
      (node (ref "C172") (pin "1") (pinfunction "1_1") (pintype "passive"))
      (node (ref "C173") (pin "1") (pinfunction "1_1") (pintype "passive"))
      (node (ref "C174") (pin "1") (pinfunction "1_1") (pintype "passive"))
      (node (ref "C175") (pin "2") (pinfunction "2_2") (pintype "passive"))
      (node (ref "C176") (pin "1") (pinfunction "1_1") (pintype "passive"))
      (node (ref "C177") (pin "1") (pinfunction "1_1") (pintype "passive"))
      (node (ref "C178") (pin "1") (pinfunction "1_1") (pintype "passive"))
      (node (ref "C180") (pin "1") (pinfunction "1_1") (pintype "passive"))
      (node (ref "C181") (pin "1") (pinfunction "1_1") (pintype "passive"))
      (node (ref "C183") (pin "1") (pinfunction "1_1") (pintype "passive"))
      (node (ref "C184") (pin "1") (pinfunction "1_1") (pintype "passive"))
      (node (ref "C186") (pin "1") (pinfunction "1_1") (pintype "passive"))
      (node (ref "C187") (pin "1") (pinfunction "1_1") (pintype "passive"))
      (node (ref "C309") (pin "1") (pinfunction "1_1") (pintype "passive"))
      (node (ref "C328") (pin "1") (pinfunction "1_1") (pintype "passive"))
      (node (ref "IC12") (pin "11") (pinfunction "VEE_11") (pintype "power_in"))
      (node (ref "IC13") (pin "10") (pinfunction "OS1_10") (pintype "input"))
      (node (ref "IC13") (pin "22") (pinfunction "GND1_22") (pintype "power_in"))
      (node (ref "IC13") (pin "PAD") (pinfunction "GND_PAD") (pintype "power_in"))
      (node (ref "IC16") (pin "37") (pinfunction "GND_37") (pintype "power_in"))
      (node (ref "IC16") (pin "44") (pinfunction "GND_44") (pintype "power_in"))
      (node (ref "IC16") (pin "59") (pinfunction "GND_59") (pintype "power_in"))
      (node (ref "IC16") (pin "PAD") (pinfunction "GND_PAD_PAD") (pintype "power_in"))
      (node (ref "R219") (pin "1") (pinfunction "1_1") (pintype "passive"))
      (node (ref "R221") (pin "1") (pinfunction "1_1") (pintype "passive"))
      (node (ref "R222") (pin "1") (pinfunction "1_1") (pintype "passive"))
      (node (ref "R226") (pin "1") (pinfunction "1_1") (pintype "passive"))
      (node (ref "R246") (pin "2") (pinfunction "2_2") (pintype "passive"))
      (node (ref "R247") (pin "2") (pinfunction "2_2") (pintype "passive"))
      (node (ref "R249") (pin "1") (pinfunction "1_1") (pintype "passive"))
      (node (ref "R255") (pin "1") (pinfunction "1_1") (pintype "passive"))
      (node (ref "R60") (pin "2") (pinfunction "2_2") (pintype "passive"))
      (node (ref "R61") (pin "2") (pinfunction "2_2") (pintype "passive"))
      (node (ref "R62") (pin "2") (pinfunction "2_2") (pintype "passive"))
      (node (ref "R64") (pin "2") (pinfunction "2_2") (pintype "passive"))
      (node (ref "R66") (pin "2") (pinfunction "2_2") (pintype "passive"))
      (node (ref "R67") (pin "2") (pinfunction "2_2") (pintype "passive"))
      (node (ref "R68") (pin "2") (pinfunction "2_2") (pintype "passive"))
      (node (ref "R69") (pin "1") (pinfunction "1_1") (pintype "passive"))
      (node (ref "R71") (pin "2") (pinfunction "2_2") (pintype "passive"))
      (node (ref "R72") (pin "2") (pinfunction "2_2") (pintype "passive"))
      (node (ref "R73") (pin "2") (pinfunction "2_2") (pintype "passive"))
      (node (ref "R76") (pin "1") (pinfunction "1_1") (pintype "passive"))
      (node (ref "R81") (pin "2") (pinfunction "2_2") (pintype "passive"))
      (node (ref "R82") (pin "2") (pinfunction "2_2") (pintype "passive"))
      (node (ref "R83") (pin "1") (pinfunction "1_1") (pintype "passive"))
      (node (ref "R84") (pin "2") (pinfunction "2_2") (pintype "passive"))
      (node (ref "R85") (pin "2") (pinfunction "2_2") (pintype "passive"))
      (node (ref "R86") (pin "1") (pinfunction "1_1") (pintype "passive"))
      (node (ref "R87") (pin "2") (pinfunction "2_2") (pintype "passive"))
      (node (ref "R88") (pin "2") (pinfunction "2_2") (pintype "passive"))
      (node (ref "R89") (pin "2") (pinfunction "2_2") (pintype "passive"))
      (node (ref "R91") (pin "2") (pinfunction "2_2") (pintype "passive"))
      (node (ref "R92") (pin "2") (pinfunction "2_2") (pintype "passive"))
      (node (ref "R93") (pin "2") (pinfunction "2_2") (pintype "passive"))
      (node (ref "R94") (pin "1") (pinfunction "1_1") (pintype "passive"))
      (node (ref "Tr3") (pin "3") (pinfunction "Sec-_3") (pintype "passive"))
      (node (ref "Tr3") (pin "4") (pinfunction "Pri-_4") (pintype "passive"))
    )
    (net (code "60") (name "Net-(C168-Pad1)") (class "Default")
      (node (ref "C168") (pin "1") (pinfunction "1_1") (pintype "passive"))
      (node (ref "R79") (pin "2") (pinfunction "2_2") (pintype "passive"))
    )
    (net (code "61") (name "Net-(IC12-Q0)") (class "Default")
      (node (ref "C90") (pin "2") (pinfunction "2_2") (pintype "passive"))
      (node (ref "IC12") (pin "1") (pinfunction "Q0_1") (pintype "open_emitter"))
      (node (ref "R93") (pin "1") (pinfunction "1_1") (pintype "passive"))
    )
    (net (code "62") (name "Net-(IC12-Q1)") (class "Default")
      (node (ref "C101") (pin "2") (pinfunction "2_2") (pintype "passive"))
      (node (ref "IC12") (pin "3") (pinfunction "Q1_3") (pintype "open_emitter"))
      (node (ref "R91") (pin "1") (pinfunction "1_1") (pintype "passive"))
    )
    (net (code "63") (name "Net-(IC12-Q2)") (class "Default")
      (node (ref "C103") (pin "2") (pinfunction "2_2") (pintype "passive"))
      (node (ref "IC12") (pin "5") (pinfunction "Q2_5") (pintype "open_emitter"))
      (node (ref "R87") (pin "1") (pinfunction "1_1") (pintype "passive"))
    )
    (net (code "64") (name "Net-(IC12-Q3)") (class "Default")
      (node (ref "C125") (pin "2") (pinfunction "2_2") (pintype "passive"))
      (node (ref "IC12") (pin "7") (pinfunction "Q3_7") (pintype "open_emitter"))
      (node (ref "R84") (pin "1") (pinfunction "1_1") (pintype "passive"))
    )
    (net (code "65") (name "Net-(IC12-Q4)") (class "Default")
      (node (ref "C139") (pin "2") (pinfunction "2_2") (pintype "passive"))
      (node (ref "IC12") (pin "9") (pinfunction "Q4_9") (pintype "open_emitter"))
      (node (ref "R81") (pin "1") (pinfunction "1_1") (pintype "passive"))
    )
    (net (code "66") (name "Net-(IC12-~{Q}0)") (class "Default")
      (node (ref "C89") (pin "2") (pinfunction "2_2") (pintype "passive"))
      (node (ref "IC12") (pin "2") (pinfunction "~{Q}0_2") (pintype "open_emitter"))
      (node (ref "R92") (pin "1") (pinfunction "1_1") (pintype "passive"))
    )
    (net (code "67") (name "Net-(IC12-~{Q}1)") (class "Default")
      (node (ref "C99") (pin "2") (pinfunction "2_2") (pintype "passive"))
      (node (ref "IC12") (pin "4") (pinfunction "~{Q}1_4") (pintype "open_emitter"))
      (node (ref "R89") (pin "1") (pinfunction "1_1") (pintype "passive"))
    )
    (net (code "68") (name "Net-(IC12-~{Q}2)") (class "Default")
      (node (ref "C102") (pin "2") (pinfunction "2_2") (pintype "passive"))
      (node (ref "IC12") (pin "6") (pinfunction "~{Q}2_6") (pintype "open_emitter"))
      (node (ref "R88") (pin "1") (pinfunction "1_1") (pintype "passive"))
    )
    (net (code "69") (name "Net-(IC12-~{Q}3)") (class "Default")
      (node (ref "C122") (pin "2") (pinfunction "2_2") (pintype "passive"))
      (node (ref "IC12") (pin "8") (pinfunction "~{Q}3_8") (pintype "open_emitter"))
      (node (ref "R85") (pin "1") (pinfunction "1_1") (pintype "passive"))
    )
    (net (code "70") (name "Net-(IC12-~{Q}4)") (class "Default")
      (node (ref "C138") (pin "2") (pinfunction "2_2") (pintype "passive"))
      (node (ref "IC12") (pin "10") (pinfunction "~{Q}4_10") (pintype "open_emitter"))
      (node (ref "R82") (pin "1") (pinfunction "1_1") (pintype "passive"))
    )
    (net (code "71") (name "Net-(IC13A-OD0)") (class "Default")
      (node (ref "IC13") (pin "13") (pinfunction "OD0_13") (pintype "input"))
      (node (ref "R64") (pin "1") (pinfunction "1_1") (pintype "passive"))
    )
    (net (code "72") (name "Net-(IC13A-OD1)") (class "Default")
      (node (ref "IC13") (pin "14") (pinfunction "OD1_14") (pintype "input"))
      (node (ref "R62") (pin "1") (pinfunction "1_1") (pintype "passive"))
    )
    (net (code "73") (name "Net-(IC13A-OD2)") (class "Default")
      (node (ref "IC13") (pin "15") (pinfunction "OD2_15") (pintype "input"))
      (node (ref "R61") (pin "1") (pinfunction "1_1") (pintype "passive"))
    )
    (net (code "74") (name "Net-(IC13A-OS0)") (class "Default")
      (node (ref "IC13") (pin "11") (pinfunction "OS0_11") (pintype "input"))
      (node (ref "R60") (pin "1") (pinfunction "1_1") (pintype "passive"))
    )
    (net (code "75") (name "Net-(IC13A-PR0)") (class "Default")
      (node (ref "IC13") (pin "25") (pinfunction "PR0_25") (pintype "input"))
      (node (ref "R66") (pin "1") (pinfunction "1_1") (pintype "passive"))
    )
    (net (code "76") (name "Net-(IC13A-PR1)") (class "Default")
      (node (ref "IC13") (pin "26") (pinfunction "PR1_26") (pintype "input"))
      (node (ref "R67") (pin "1") (pinfunction "1_1") (pintype "passive"))
    )
    (net (code "77") (name "Net-(IC13A-REG_CAP1)") (class "Default")
      (node (ref "C156") (pin "1") (pinfunction "1_1") (pintype "passive"))
      (node (ref "IC13") (pin "19") (pinfunction "REG_CAP1_19") (pintype "passive"))
    )
    (net (code "78") (name "Net-(IC13A-REG_CAP2)") (class "Default")
      (node (ref "C155") (pin "1") (pinfunction "1_1") (pintype "passive"))
      (node (ref "IC13") (pin "17") (pinfunction "REG_CAP2_17") (pintype "passive"))
    )
    (net (code "79") (name "Net-(IC13A-XIN)") (class "Default")
      (node (ref "C154") (pin "1") (pinfunction "1_1") (pintype "passive"))
      (node (ref "IC13") (pin "21") (pinfunction "XIN_21") (pintype "input"))
    )
    (net (code "80") (name "Net-(IC13A-~{RSTN})") (class "Default")
      (node (ref "C328") (pin "2") (pinfunction "2_2") (pintype "passive"))
      (node (ref "IC13") (pin "12") (pinfunction "~{RSTN}_12") (pintype "input"))
    )
    (net (code "81") (name "Net-(IC13B-VCC_PLL1)") (class "Default")
      (node (ref "C140") (pin "1") (pinfunction "1_1") (pintype "passive"))
      (node (ref "C141") (pin "2") (pinfunction "2_2") (pintype "passive"))
      (node (ref "C142") (pin "2") (pinfunction "2_2") (pintype "passive"))
      (node (ref "IC13") (pin "16") (pinfunction "VCC_PLL2_16") (pintype "power_in"))
      (node (ref "IC13") (pin "18") (pinfunction "VCC_PLL1_18") (pintype "power_in"))
      (node (ref "IC13") (pin "9") (pinfunction "VCC_VCO_9") (pintype "power_in"))
      (node (ref "L6") (pin "1") (pinfunction "1_1") (pintype "passive"))
    )
    (net (code "82") (name "Net-(IC16A-BYPASS)") (class "Default")
      (node (ref "C164") (pin "1") (pinfunction "1_1") (pintype "passive"))
      (node (ref "C165") (pin "2") (pinfunction "2_2") (pintype "passive"))
      (node (ref "C170") (pin "1") (pinfunction "1_1") (pintype "passive"))
      (node (ref "IC16") (pin "10") (pinfunction "BYPASS_10") (pintype "output"))
      (node (ref "R79") (pin "1") (pinfunction "1_1") (pintype "passive"))
    )
    (net (code "83") (name "Net-(IC16A-CP)") (class "Default")
      (node (ref "C168") (pin "2") (pinfunction "2_2") (pintype "passive"))
      (node (ref "C170") (pin "2") (pinfunction "2_2") (pintype "passive"))
      (node (ref "IC16") (pin "5") (pinfunction "CP_5") (pintype "output"))
      (node (ref "R80") (pin "2") (pinfunction "2_2") (pintype "passive"))
    )
    (net (code "84") (name "Net-(IC16A-CPRSET)") (class "Default")
      (node (ref "IC16") (pin "62") (pinfunction "CPRSET_62") (pintype "passive"))
      (node (ref "R86") (pin "2") (pinfunction "2_2") (pintype "passive"))
    )
    (net (code "85") (name "Net-(IC16A-LD)") (class "Default")
      (node (ref "IC16") (pin "3") (pinfunction "LD_3") (pintype "output"))
      (node (ref "R220") (pin "1") (pinfunction "1_1") (pintype "passive"))
    )
    (net (code "86") (name "Net-(IC16A-LF)") (class "Default")
      (node (ref "C164") (pin "2") (pinfunction "2_2") (pintype "passive"))
      (node (ref "IC16") (pin "9") (pinfunction "LF_9") (pintype "input"))
      (node (ref "R80") (pin "1") (pinfunction "1_1") (pintype "passive"))
    )
    (net (code "87") (name "Net-(IC16A-OUT0)") (class "Default")
      (node (ref "C153") (pin "2") (pinfunction "2_2") (pintype "passive"))
      (node (ref "IC16") (pin "56") (pinfunction "OUT0_56") (pintype "output"))
      (node (ref "R73") (pin "1") (pinfunction "1_1") (pintype "passive"))
    )
    (net (code "88") (name "Net-(IC16A-OUT1)") (class "Default")
      (node (ref "C327") (pin "2") (pinfunction "2_2") (pintype "passive"))
      (node (ref "IC16") (pin "53") (pinfunction "OUT1_53") (pintype "output"))
      (node (ref "R247") (pin "1") (pinfunction "1_1") (pintype "passive"))
    )
    (net (code "89") (name "Net-(IC16A-OUT2)") (class "Default")
      (node (ref "C150") (pin "2") (pinfunction "2_2") (pintype "passive"))
      (node (ref "IC16") (pin "43") (pinfunction "OUT2_43") (pintype "output"))
      (node (ref "R71") (pin "1") (pinfunction "1_1") (pintype "passive"))
    )
    (net (code "90") (name "Net-(IC16A-OUT3)") (class "Default")
      (node (ref "IC16") (pin "40") (pinfunction "OUT3_40") (pintype "output"))
      (node (ref "R255") (pin "2") (pinfunction "2_2") (pintype "passive"))
      (node (ref "R78") (pin "1") (pinfunction "1_1") (pintype "passive"))
    )
    (net (code "91") (name "Net-(IC16A-OUT5)") (class "Default")
      (node (ref "IC16") (pin "28") (pinfunction "OUT5_28") (pintype "output"))
      (node (ref "R70") (pin "1") (pinfunction "1_1") (pintype "passive"))
      (node (ref "R94") (pin "2") (pinfunction "2_2") (pintype "passive"))
    )
    (net (code "92") (name "Net-(IC16A-OUT9_(OUT9A))") (class "Default")
      (node (ref "C422") (pin "1") (pinfunction "1_1") (pintype "passive"))
      (node (ref "IC16") (pin "35") (pinfunction "OUT9_(OUT9A)_35") (pintype "output"))
    )
    (net (code "93") (name "Net-(IC16A-REFIN_(REF1))") (class "Default")
      (node (ref "C185") (pin "2") (pinfunction "2_2") (pintype "passive"))
      (node (ref "IC16") (pin "64") (pinfunction "REFIN_(REF1)_64") (pintype "input"))
    )
    (net (code "94") (name "Net-(IC16A-RSET)") (class "Default")
      (node (ref "IC16") (pin "58") (pinfunction "RSET_58") (pintype "passive"))
      (node (ref "R83") (pin "2") (pinfunction "2_2") (pintype "passive"))
    )
    (net (code "95") (name "Net-(IC16A-SDIO)") (class "Default")
      (node (ref "IC16") (pin "22") (pinfunction "SDIO_22") (pintype "bidirectional"))
      (node (ref "R224") (pin "1") (pinfunction "1_1") (pintype "passive"))
    )
    (net (code "96") (name "Net-(IC16A-SDO)") (class "Default")
      (node (ref "IC16") (pin "21") (pinfunction "SDO_21") (pintype "output"))
      (node (ref "R223") (pin "1") (pinfunction "1_1") (pintype "passive"))
    )
    (net (code "97") (name "Net-(IC16A-STATUS)") (class "Default")
      (node (ref "IC16") (pin "6") (pinfunction "STATUS_6") (pintype "output"))
      (node (ref "R225") (pin "1") (pinfunction "1_1") (pintype "passive"))
    )
    (net (code "98") (name "Net-(IC16A-~{OUT0})") (class "Default")
      (node (ref "C152") (pin "2") (pinfunction "2_2") (pintype "passive"))
      (node (ref "IC16") (pin "55") (pinfunction "~{OUT0}_55") (pintype "output"))
      (node (ref "R72") (pin "1") (pinfunction "1_1") (pintype "passive"))
    )
    (net (code "99") (name "Net-(IC16A-~{OUT1})") (class "Default")
      (node (ref "C158") (pin "2") (pinfunction "2_2") (pintype "passive"))
      (node (ref "IC16") (pin "52") (pinfunction "~{OUT1}_52") (pintype "output"))
      (node (ref "R246") (pin "1") (pinfunction "1_1") (pintype "passive"))
    )
    (net (code "100") (name "Net-(IC16A-~{OUT2})") (class "Default")
      (node (ref "C149") (pin "2") (pinfunction "2_2") (pintype "passive"))
      (node (ref "IC16") (pin "42") (pinfunction "~{OUT2}_42") (pintype "output"))
      (node (ref "R68") (pin "1") (pinfunction "1_1") (pintype "passive"))
    )
    (net (code "101") (name "Net-(IC16A-~{OUT3})") (class "Default")
      (node (ref "IC16") (pin "39") (pinfunction "~{OUT3}_39") (pintype "output"))
      (node (ref "R63") (pin "1") (pinfunction "1_1") (pintype "passive"))
      (node (ref "R76") (pin "2") (pinfunction "2_2") (pintype "passive"))
    )
    (net (code "102") (name "Net-(IC16A-~{OUT5})") (class "Default")
      (node (ref "IC16") (pin "29") (pinfunction "~{OUT5}_29") (pintype "output"))
      (node (ref "R30") (pin "1") (pinfunction "1_1") (pintype "passive"))
      (node (ref "R69") (pin "2") (pinfunction "2_2") (pintype "passive"))
    )
    (net (code "103") (name "Net-(IC16A-~{REFIN}_(REF2))") (class "Default")
      (node (ref "C188") (pin "2") (pinfunction "2_2") (pintype "passive"))
      (node (ref "IC16") (pin "63") (pinfunction "~{REFIN}_(REF2)_63") (pintype "input"))
    )
    (net (code "104") (name "Net-(IC16B-VCP)") (class "Default")
      (node (ref "C160") (pin "1") (pinfunction "1_1") (pintype "passive"))
      (node (ref "C161") (pin "2") (pinfunction "2_2") (pintype "passive"))
      (node (ref "C163") (pin "2") (pinfunction "2_2") (pintype "passive"))
      (node (ref "IC16") (pin "4") (pinfunction "VCP_4") (pintype "power_in"))
      (node (ref "L8") (pin "1") (pinfunction "1_1") (pintype "passive"))
    )
    (net (code "105") (name "Net-(Tr3-Pri+)") (class "Default")
      (node (ref "C422") (pin "2") (pinfunction "2_2") (pintype "passive"))
      (node (ref "R65") (pin "2") (pinfunction "2_2") (pintype "passive"))
      (node (ref "Tr3") (pin "6") (pinfunction "Pri+_6") (pintype "passive"))
    )
    (net (code "106") (name "unconnected-(IC12-VBB-Pad15)") (class "Default")
      (node (ref "IC12") (pin "15") (pinfunction "VBB_15") (pintype "power_in"))
    )
    (net (code "107") (name "unconnected-(IC13A-OSC_OUT-Pad23)") (class "Default")
      (node (ref "IC13") (pin "23") (pinfunction "OSC_OUT_23") (pintype "output"))
    )
    (net (code "108") (name "unconnected-(IC16A-CLK-Pad13)") (class "Default")
      (node (ref "IC16") (pin "13") (pinfunction "CLK_13") (pintype "input+no_connect"))
    )
    (net (code "109") (name "unconnected-(IC16A-REFMON-Pad2)") (class "Default")
      (node (ref "IC16") (pin "2") (pinfunction "REFMON_2") (pintype "output"))
    )
    (net (code "110") (name "unconnected-(IC16A-~{CLK}-Pad14)") (class "Default")
      (node (ref "IC16") (pin "14") (pinfunction "~{CLK}_14") (pintype "input+no_connect"))
    )
    (net (code "111") (name "unconnected-(IC16A-~{OUT9}_(OUT9B)-Pad36)") (class "Default")
      (node (ref "IC16") (pin "36") (pinfunction "~{OUT9}_(OUT9B)_36") (pintype "output"))
    )
  )
)
